# Copia_de_UC3844_-_CON_TEST.net
KiCad netlist of a schematic drawn in Altium Designer
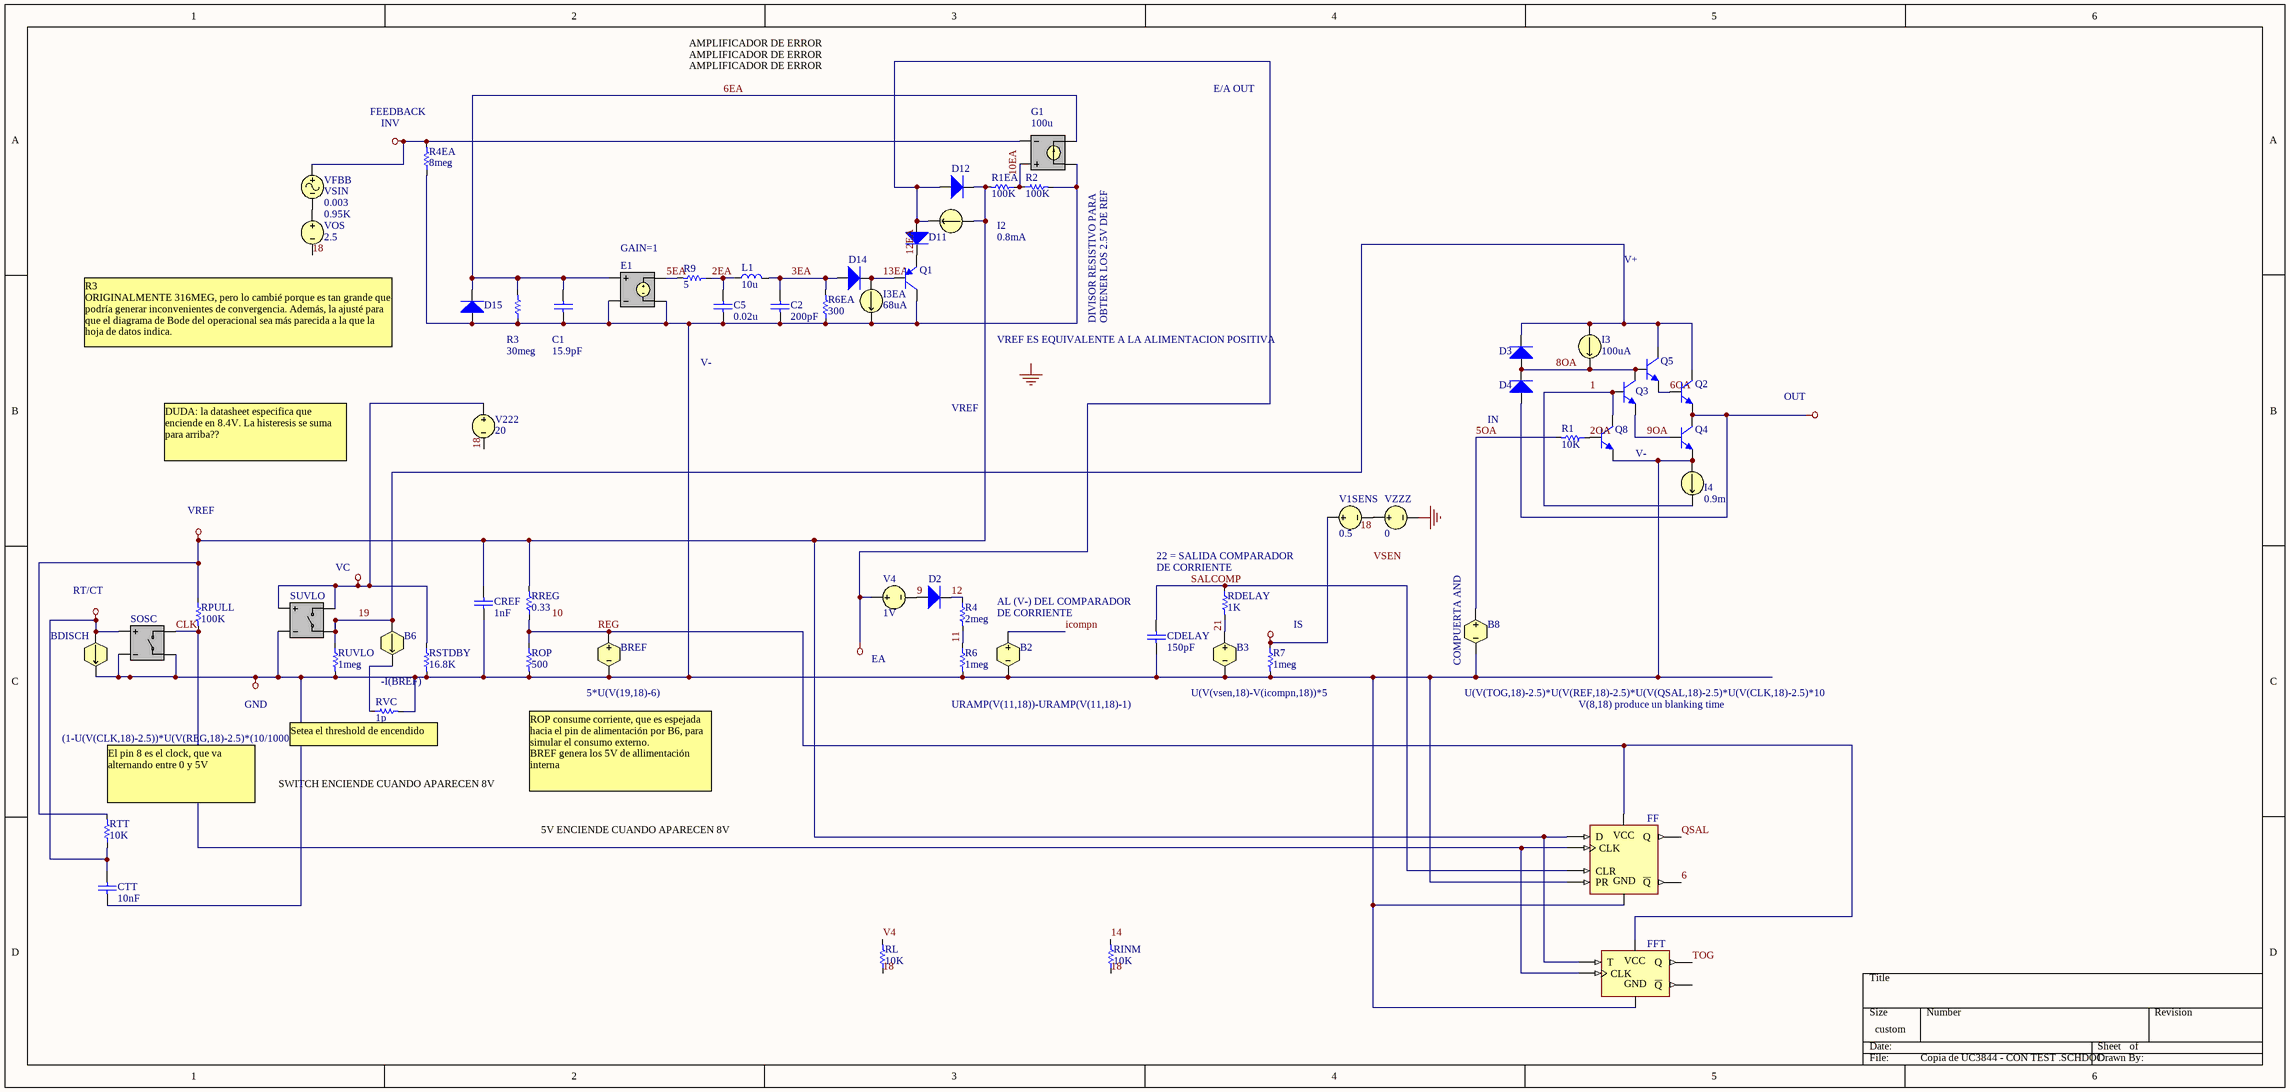
[diagram p0: Copia de UC3844 - CON TEST .SCHDOC]

(export (version "E")
  (design (tool "Eeschema 10.0.6"))
  (components
    (comp (ref "B2")
      (value "BVSRC")
      (description "Non-Linear Dependent Voltage Source")
      (fields
        (field (name "EQUATION") "URAMP(V(11,18))-URAMP(V(11,18)-1)")
        (field (name "PUBLISHER") "Altium Limited")
      )
      (libsource (lib "Simulation Sources") (part "BVSRC"))
    )
    (comp (ref "B3")
      (value "BVSRC")
      (description "Non-Linear Dependent Voltage Source")
      (fields
        (field (name "EQUATION") "U(V(vsen,18)-V(icompn,18))*5")
        (field (name "PUBLISHER") "Altium Limited")
      )
      (libsource (lib "Simulation Sources") (part "BVSRC"))
    )
    (comp (ref "B6")
      (value "BISRC")
      (description "Non-Linear Dependent Current Source")
      (fields (field (name "EQUATION") "-I(BREF)") (field (name "PUBLISHER") "Altium Limited"))
      (libsource (lib "Simulation Sources") (part "BISRC"))
    )
    (comp (ref "B8")
      (value "BVSRC")
      (description "Non-Linear Dependent Voltage Source")
      (fields
        (field (name "EQUATION") "U(V(TOG,18)-2.5)*U(V(REF,18)-2.5)*U(V(QSAL,18)-2.5)*U(V(CLK,18)-2.5)*10")
        (field (name "PUBLISHER") "Altium Limited")
      )
      (libsource (lib "Simulation Sources") (part "BVSRC"))
    )
    (comp (ref "BDISCH")
      (value "BISRC")
      (description "Non-Linear Dependent Current Source")
      (fields
        (field (name "EQUATION") "(1-U(V(CLK,18)-2.5))*U(V(REG,18)-2.5)*(10/1000)")
        (field (name "PUBLISHER") "Altium Limited")
      )
      (libsource (lib "Simulation Sources") (part "BISRC"))
    )
    (comp (ref "BREF")
      (value "BVSRC")
      (description "Non-Linear Dependent Voltage Source")
      (fields (field (name "EQUATION") "5*U(V(19,18)-6)") (field (name "PUBLISHER") "Altium Limited"))
      (libsource (lib "Simulation Sources") (part "BVSRC"))
    )
    (comp (ref "C1")
      (value "15.9pF")
      (footprint "0805")
      (description "Capacitor")
      (fields (field (name "VOLTAGE") "50V") (field (name "Comment") "Cap"))
      (libsource (lib "FEDE") (part "Cap"))
    )
    (comp (ref "C2")
      (value "200pF")
      (footprint "0805")
      (description "Capacitor")
      (fields (field (name "VOLTAGE") "50V") (field (name "Comment") "Cap"))
      (libsource (lib "FEDE") (part "Cap"))
    )
    (comp (ref "C5")
      (value "0.02u")
      (footprint "0805")
      (description "Capacitor")
      (fields (field (name "VOLTAGE") "50V") (field (name "Comment") "Cap"))
      (libsource (lib "FEDE") (part "Cap"))
    )
    (comp (ref "CDELAY")
      (value "150pF")
      (footprint "0805")
      (description "Capacitor")
      (fields (field (name "VOLTAGE") "50V") (field (name "Comment") "Cap"))
      (libsource (lib "FEDE") (part "Cap"))
    )
    (comp (ref "CREF")
      (value "1nF")
      (footprint "0805")
      (description "Capacitor")
      (fields (field (name "VOLTAGE") "50V") (field (name "Comment") "Cap"))
      (libsource (lib "FEDE") (part "Cap"))
    )
    (comp (ref "CTT")
      (value "10nF")
      (footprint "0805")
      (description "Capacitor")
      (fields (field (name "VOLTAGE") "50V") (field (name "Comment") "Cap"))
      (libsource (lib "FEDE") (part "Cap"))
    )
    (comp (ref "D2")
      (value "Diode")
      (footprint "diode400")
      (description "Diodo")
      (libsource (lib "FEDE") (part "Diode"))
    )
    (comp (ref "D3")
      (value "Diode")
      (footprint "diode400")
      (description "Diodo")
      (libsource (lib "FEDE") (part "Diode"))
    )
    (comp (ref "D4")
      (value "Diode")
      (footprint "diode400")
      (description "Diodo")
      (libsource (lib "FEDE") (part "Diode"))
    )
    (comp (ref "D11")
      (value "Diode")
      (footprint "diode400")
      (description "Diodo")
      (libsource (lib "FEDE") (part "Diode"))
    )
    (comp (ref "D12")
      (value "Diode")
      (footprint "diode400")
      (description "Diodo")
      (libsource (lib "FEDE") (part "Diode"))
    )
    (comp (ref "D14")
      (value "Diode")
      (footprint "diode400")
      (description "Diodo")
      (libsource (lib "FEDE") (part "Diode"))
    )
    (comp (ref "D15")
      (value "Diode")
      (footprint "diode400")
      (description "Diodo")
      (libsource (lib "FEDE") (part "Diode"))
    )
    (comp (ref "E1")
      (value "ESRC")
      (description "Voltage Controlled Voltage Source")
      (fields (field (name "PUBLISHER") "Altium Limited"))
      (libsource (lib "Simulation Sources") (part "ESRC"))
    )
    (comp (ref "FF")
      (value "FFSRV2")
      (description "D-Type Positive-Edge-Triggered Flip-Flop with Clear and Preset (simulación)")
      (libsource (lib "FEDE") (part "FFSRV2"))
    )
    (comp (ref "FFT")
      (value "FFT")
      (description "Positive-Edge-Triggered Flip-Flop T (simulación)")
      (libsource (lib "FEDE") (part "FFT"))
    )
    (comp (ref "G1")
      (value "GSRC")
      (description "Voltage Controlled Current Source")
      (fields (field (name "GAIN") "100u") (field (name "PUBLISHER") "Altium Limited"))
      (libsource (lib "Simulation Sources") (part "GSRC"))
    )
    (comp (ref "I2")
      (value "0.8mA")
      (description "Current Source")
      (fields (field (name "Comment") "ISRC") (field (name "PUBLISHER") "Altium Limited"))
      (libsource (lib "Simulation Sources") (part "ISRC"))
    )
    (comp (ref "I3")
      (value "100uA")
      (description "Current Source")
      (fields (field (name "Comment") "ISRC") (field (name "PUBLISHER") "Altium Limited"))
      (libsource (lib "Simulation Sources") (part "ISRC"))
    )
    (comp (ref "I3EA")
      (value "68uA")
      (description "Current Source")
      (fields (field (name "Comment") "ISRC") (field (name "PUBLISHER") "Altium Limited"))
      (libsource (lib "Simulation Sources") (part "ISRC"))
    )
    (comp (ref "I4")
      (value "0.9m")
      (description "Current Source")
      (fields (field (name "Comment") "ISRC") (field (name "PUBLISHER") "Altium Limited"))
      (libsource (lib "Simulation Sources") (part "ISRC"))
    )
    (comp (ref "L1")
      (value "10u")
      (footprint "TOROIDE TN14-9-5")
      (description "Inductor")
      (fields (field (name "Comment") "Inductor2"))
      (libsource (lib "FEDE") (part "Inductor2"))
    )
    (comp (ref "Q1")
      (value "PNP")
      (footprint "SOT23")
      (description "PNP Bipolar Transistor")
      (libsource (lib "FEDE") (part "PNP"))
    )
    (comp (ref "Q2")
      (value "NPN")
      (footprint "SOT23")
      (description "NPN Bipolar Transistor")
      (libsource (lib "FEDE") (part "NPN"))
    )
    (comp (ref "Q3")
      (value "NPN")
      (footprint "SOT23")
      (description "NPN Bipolar Transistor")
      (libsource (lib "FEDE") (part "NPN"))
    )
    (comp (ref "Q4")
      (value "NPN")
      (footprint "SOT23")
      (description "NPN Bipolar Transistor")
      (libsource (lib "FEDE") (part "NPN"))
    )
    (comp (ref "Q5")
      (value "NPN")
      (footprint "SOT23")
      (description "NPN Bipolar Transistor")
      (libsource (lib "FEDE") (part "NPN"))
    )
    (comp (ref "Q8")
      (value "NPN")
      (footprint "SOT23")
      (description "NPN Bipolar Transistor")
      (libsource (lib "FEDE") (part "NPN"))
    )
    (comp (ref "R1")
      (value "10K")
      (footprint "0805")
      (description "Resistor")
      (fields (field (name "POWER") "0.25W") (field (name "Comment") "Res"))
      (libsource (lib "FEDE") (part "Res"))
    )
    (comp (ref "R1EA")
      (value "100K")
      (footprint "0805")
      (description "Resistor")
      (fields (field (name "POWER") "0.25W") (field (name "Comment") "Res"))
      (libsource (lib "FEDE") (part "Res"))
    )
    (comp (ref "R2")
      (value "100K")
      (footprint "0805")
      (description "Resistor")
      (fields (field (name "POWER") "0.25W") (field (name "Comment") "Res"))
      (libsource (lib "FEDE") (part "Res"))
    )
    (comp (ref "R3")
      (value "30meg")
      (footprint "0805")
      (description "Resistor")
      (fields (field (name "POWER") "0.25W") (field (name "Comment") "Res"))
      (libsource (lib "FEDE") (part "Res"))
    )
    (comp (ref "R4")
      (value "2meg")
      (footprint "0805")
      (description "Resistor")
      (fields (field (name "POWER") "0.25W") (field (name "Comment") "Res"))
      (libsource (lib "FEDE") (part "Res"))
    )
    (comp (ref "R4EA")
      (value "8meg")
      (footprint "0805")
      (description "Resistor")
      (fields (field (name "POWER") "0.25W") (field (name "Comment") "Res"))
      (libsource (lib "FEDE") (part "Res"))
    )
    (comp (ref "R6")
      (value "1meg")
      (footprint "0805")
      (description "Resistor")
      (fields (field (name "POWER") "0.25W") (field (name "Comment") "Res"))
      (libsource (lib "FEDE") (part "Res"))
    )
    (comp (ref "R6EA")
      (value "300")
      (footprint "0805")
      (description "Resistor")
      (fields (field (name "POWER") "0.25W") (field (name "Comment") "Res"))
      (libsource (lib "FEDE") (part "Res"))
    )
    (comp (ref "R7")
      (value "1meg")
      (footprint "0805")
      (description "Resistor")
      (fields (field (name "POWER") "0.25W") (field (name "Comment") "Res"))
      (libsource (lib "FEDE") (part "Res"))
    )
    (comp (ref "R9")
      (value "5")
      (footprint "0805")
      (description "Resistor")
      (fields (field (name "POWER") "0.25W") (field (name "Comment") "Res"))
      (libsource (lib "FEDE") (part "Res"))
    )
    (comp (ref "RDELAY")
      (value "1K")
      (footprint "0805")
      (description "Resistor")
      (fields (field (name "POWER") "0.25W") (field (name "Comment") "Res"))
      (libsource (lib "FEDE") (part "Res"))
    )
    (comp (ref "RINM")
      (value "10K")
      (footprint "0805")
      (description "Resistor")
      (fields (field (name "POWER") "0.25W") (field (name "Comment") "Res"))
      (libsource (lib "FEDE") (part "Res"))
    )
    (comp (ref "RL")
      (value "10K")
      (footprint "0805")
      (description "Resistor")
      (fields (field (name "POWER") "0.25W") (field (name "Comment") "Res"))
      (libsource (lib "FEDE") (part "Res"))
    )
    (comp (ref "ROP")
      (value "500")
      (footprint "0805")
      (description "Resistor")
      (fields (field (name "POWER") "0.25W") (field (name "Comment") "Res"))
      (libsource (lib "FEDE") (part "Res"))
    )
    (comp (ref "RPULL")
      (value "100K")
      (footprint "0805")
      (description "Resistor")
      (fields (field (name "POWER") "0.25W") (field (name "Comment") "Res"))
      (libsource (lib "FEDE") (part "Res"))
    )
    (comp (ref "RREG")
      (value "0.33")
      (footprint "0805")
      (description "Resistor")
      (fields (field (name "POWER") "0.25W") (field (name "Comment") "Res"))
      (libsource (lib "FEDE") (part "Res"))
    )
    (comp (ref "RSTDBY")
      (value "16.8K")
      (footprint "0805")
      (description "Resistor")
      (fields (field (name "POWER") "0.25W") (field (name "Comment") "Res"))
      (libsource (lib "FEDE") (part "Res"))
    )
    (comp (ref "RTT")
      (value "10K")
      (footprint "0805")
      (description "Resistor")
      (fields (field (name "POWER") "0.25W") (field (name "Comment") "Res"))
      (libsource (lib "FEDE") (part "Res"))
    )
    (comp (ref "RUVLO")
      (value "1meg")
      (footprint "0805")
      (description "Resistor")
      (fields (field (name "POWER") "0.25W") (field (name "Comment") "Res"))
      (libsource (lib "FEDE") (part "Res"))
    )
    (comp (ref "RVC")
      (value "1p")
      (footprint "0805")
      (description "Resistor")
      (fields (field (name "POWER") "0.25W") (field (name "Comment") "Res"))
      (libsource (lib "FEDE") (part "Res"))
    )
    (comp (ref "SOSC")
      (value "VSW")
      (description "Voltage Controlled Switch (simulación)")
      (libsource (lib "FEDE") (part "VSW"))
    )
    (comp (ref "SUVLO")
      (value "VSW")
      (description "Voltage Controlled Switch (simulación)")
      (libsource (lib "FEDE") (part "VSW"))
    )
    (comp (ref "V1SENS")
      (value "0.5")
      (description "Voltage Source")
      (fields (field (name "Comment") "VSRC") (field (name "PUBLISHER") "Altium Limited"))
      (libsource (lib "Simulation Sources") (part "VSRC"))
    )
    (comp (ref "V4")
      (value "1V")
      (description "Voltage Source")
      (fields (field (name "Comment") "VSRC") (field (name "PUBLISHER") "Altium Limited"))
      (libsource (lib "Simulation Sources") (part "VSRC"))
    )
    (comp (ref "V222")
      (value "20")
      (description "Voltage Source")
      (fields (field (name "Comment") "VSRC") (field (name "PUBLISHER") "Altium Limited"))
      (libsource (lib "Simulation Sources") (part "VSRC"))
    )
    (comp (ref "VFBB")
      (value "VSIN")
      (description "Sinusoidal Voltage Source")
      (fields
        (field (name "AMPLITUDE") "0.003")
        (field (name "FREQUENCY") "0.95K")
        (field (name "PUBLISHER") "Altium Limited")
      )
      (libsource (lib "Simulation Sources") (part "VSIN"))
    )
    (comp (ref "VOS")
      (value "2.5")
      (description "Voltage Source")
      (fields (field (name "Comment") "VSRC") (field (name "PUBLISHER") "Altium Limited"))
      (libsource (lib "Simulation Sources") (part "VSRC"))
    )
    (comp (ref "VZZZ")
      (value "0")
      (description "Voltage Source")
      (fields (field (name "Comment") "VSRC") (field (name "PUBLISHER") "Altium Limited"))
      (libsource (lib "Simulation Sources") (part "VSRC"))
    )
  )
  (nets
    (net (code "1") (name "/1") (class "Default")
      (node (ref "I4") (pin "2") (pinfunction "2_2") (pintype "passive"))
      (node (ref "Q3") (pin "2") (pinfunction "B_2") (pintype "passive"))
      (node (ref "Q8") (pin "1") (pinfunction "C_1") (pintype "passive"))
    )
    (net (code "2") (name "/2EA") (class "Default")
      (node (ref "C5") (pin "2") (pinfunction "2_2") (pintype "passive"))
      (node (ref "L1") (pin "1") (pinfunction "1_1") (pintype "passive"))
      (node (ref "R9") (pin "1") (pinfunction "1_1") (pintype "passive"))
    )
    (net (code "3") (name "/2OA") (class "Default")
      (node (ref "Q8") (pin "2") (pinfunction "B_2") (pintype "passive"))
      (node (ref "R1") (pin "1") (pinfunction "1_1") (pintype "passive"))
    )
    (net (code "4") (name "/3EA") (class "Default")
      (node (ref "C2") (pin "2") (pinfunction "2_2") (pintype "passive"))
      (node (ref "D14") (pin "1") (pinfunction "1_1") (pintype "passive"))
      (node (ref "L1") (pin "2") (pinfunction "2_2") (pintype "passive"))
      (node (ref "R6EA") (pin "2") (pinfunction "2_2") (pintype "passive"))
    )
    (net (code "5") (name "/5EA") (class "Default")
      (node (ref "E1") (pin "3") (pinfunction "N+_3") (pintype "passive"))
      (node (ref "R9") (pin "2") (pinfunction "2_2") (pintype "passive"))
    )
    (net (code "6") (name "/5OA") (class "Default")
      (node (ref "B8") (pin "1") (pinfunction "1_1") (pintype "passive"))
      (node (ref "R1") (pin "2") (pinfunction "2_2") (pintype "passive"))
    )
    (net (code "7") (name "/6") (class "Default")
      (node (ref "FF") (pin "6") (pinfunction "~{Q}_6") (pintype "output"))
    )
    (net (code "8") (name "/6EA") (class "Default")
      (node (ref "C1") (pin "2") (pinfunction "2_2") (pintype "passive"))
      (node (ref "D15") (pin "2") (pinfunction "2_2") (pintype "passive"))
      (node (ref "E1") (pin "1") (pinfunction "NC+_1") (pintype "passive"))
      (node (ref "G1") (pin "4") (pinfunction "N-_4") (pintype "passive"))
      (node (ref "R3") (pin "2") (pinfunction "2_2") (pintype "passive"))
    )
    (net (code "9") (name "/6OA") (class "Default")
      (node (ref "Q2") (pin "2") (pinfunction "B_2") (pintype "passive"))
      (node (ref "Q5") (pin "3") (pinfunction "E_3") (pintype "passive"))
    )
    (net (code "10") (name "/8OA") (class "Default")
      (node (ref "D3") (pin "1") (pinfunction "1_1") (pintype "passive"))
      (node (ref "D4") (pin "2") (pinfunction "2_2") (pintype "passive"))
      (node (ref "I3") (pin "2") (pinfunction "2_2") (pintype "passive"))
      (node (ref "Q3") (pin "1") (pinfunction "C_1") (pintype "passive"))
      (node (ref "Q5") (pin "2") (pinfunction "B_2") (pintype "passive"))
    )
    (net (code "11") (name "/9") (class "Default")
      (node (ref "D2") (pin "1") (pinfunction "1_1") (pintype "passive"))
      (node (ref "V4") (pin "2") (pinfunction "2_2") (pintype "passive"))
    )
    (net (code "12") (name "/9OA") (class "Default")
      (node (ref "Q3") (pin "3") (pinfunction "E_3") (pintype "passive"))
      (node (ref "Q4") (pin "2") (pinfunction "B_2") (pintype "passive"))
    )
    (net (code "14") (name "/10EA") (class "Default")
      (node (ref "G1") (pin "1") (pinfunction "NC+_1") (pintype "passive"))
      (node (ref "R1EA") (pin "1") (pinfunction "1_1") (pintype "passive"))
      (node (ref "R2") (pin "1") (pinfunction "1_1") (pintype "passive"))
    )
    (net (code "15") (name "/11") (class "Default")
      (node (ref "R4") (pin "2") (pinfunction "2_2") (pintype "passive"))
      (node (ref "R6") (pin "1") (pinfunction "1_1") (pintype "passive"))
    )
    (net (code "16") (name "/12") (class "Default")
      (node (ref "D2") (pin "2") (pinfunction "2_2") (pintype "passive"))
      (node (ref "R4") (pin "1") (pinfunction "1_1") (pintype "passive"))
    )
    (net (code "17") (name "/12EA") (class "Default")
      (node (ref "D11") (pin "2") (pinfunction "2_2") (pintype "passive"))
      (node (ref "Q1") (pin "3") (pinfunction "E_3") (pintype "passive"))
    )
    (net (code "18") (name "/13EA") (class "Default")
      (node (ref "D14") (pin "2") (pinfunction "2_2") (pintype "passive"))
      (node (ref "I3EA") (pin "1") (pinfunction "1_1") (pintype "passive"))
      (node (ref "Q1") (pin "2") (pinfunction "B_2") (pintype "passive"))
    )
    (net (code "19") (name "/14") (class "Default")
      (node (ref "RINM") (pin "2") (pinfunction "2_2") (pintype "passive"))
    )
    (net (code "20") (name "/19") (class "Default")
      (node (ref "B6") (pin "1") (pinfunction "1_1") (pintype "passive"))
      (node (ref "D3") (pin "2") (pinfunction "2_2") (pintype "passive"))
      (node (ref "I3") (pin "1") (pinfunction "1_1") (pintype "passive"))
      (node (ref "Q2") (pin "1") (pinfunction "C_1") (pintype "passive"))
      (node (ref "Q5") (pin "1") (pinfunction "C_1") (pintype "passive"))
      (node (ref "RUVLO") (pin "1") (pinfunction "1_1") (pintype "passive"))
      (node (ref "SUVLO") (pin "4") (pinfunction "N2-_4") (pintype "passive"))
    )
    (net (code "21") (name "/21") (class "Default")
      (node (ref "B3") (pin "1") (pinfunction "1_1") (pintype "passive"))
      (node (ref "RDELAY") (pin "2") (pinfunction "2_2") (pintype "passive"))
    )
    (net (code "22") (name "/CLK") (class "Default")
      (node (ref "FF") (pin "3") (pinfunction "CLK_3") (pintype "input"))
      (node (ref "FFT") (pin "2") (pinfunction "CLK_2") (pintype "input"))
      (node (ref "RPULL") (pin "2") (pinfunction "2_2") (pintype "passive"))
      (node (ref "SOSC") (pin "3") (pinfunction "N2+_3") (pintype "passive"))
    )
    (net (code "23") (name "/QSAL") (class "Default")
      (node (ref "FF") (pin "5") (pinfunction "Q_5") (pintype "output"))
    )
    (net (code "24") (name "/REG") (class "Default")
      (node (ref "BREF") (pin "1") (pinfunction "1_1") (pintype "passive"))
      (node (ref "FF") (pin "14") (pinfunction "VCC_14") (pintype "power_in"))
      (node (ref "FFT") (pin "5") (pinfunction "VCC_5") (pintype "power_in"))
      (node (ref "ROP") (pin "1") (pinfunction "1_1") (pintype "passive"))
      (node (ref "RREG") (pin "1") (pinfunction "1_1") (pintype "passive"))
    )
    (net (code "25") (name "/SALCOMP") (class "Default")
      (node (ref "CDELAY") (pin "2") (pinfunction "2_2") (pintype "passive"))
      (node (ref "FF") (pin "1") (pinfunction "CLR_1") (pintype "input"))
      (node (ref "RDELAY") (pin "1") (pinfunction "1_1") (pintype "passive"))
    )
    (net (code "26") (name "/TOG") (class "Default")
      (node (ref "FFT") (pin "3") (pinfunction "Q_3") (pintype "output"))
    )
    (net (code "27") (name "/V4") (class "Default")
      (node (ref "RL") (pin "2") (pinfunction "2_2") (pintype "passive"))
    )
    (net (code "28") (name "/icompn") (class "Default")
      (node (ref "B2") (pin "1") (pinfunction "1_1") (pintype "passive"))
    )
    (net (code "29") (name "18") (class "Default")
      (node (ref "B2") (pin "2") (pinfunction "2_2") (pintype "passive"))
      (node (ref "B3") (pin "2") (pinfunction "2_2") (pintype "passive"))
      (node (ref "B8") (pin "2") (pinfunction "2_2") (pintype "passive"))
      (node (ref "BDISCH") (pin "2") (pinfunction "2_2") (pintype "passive"))
      (node (ref "BREF") (pin "2") (pinfunction "2_2") (pintype "passive"))
      (node (ref "C1") (pin "1") (pinfunction "1_1") (pintype "passive"))
      (node (ref "C2") (pin "1") (pinfunction "1_1") (pintype "passive"))
      (node (ref "C5") (pin "1") (pinfunction "1_1") (pintype "passive"))
      (node (ref "CDELAY") (pin "1") (pinfunction "1_1") (pintype "passive"))
      (node (ref "CREF") (pin "1") (pinfunction "1_1") (pintype "passive"))
      (node (ref "CTT") (pin "1") (pinfunction "1_1") (pintype "passive"))
      (node (ref "D15") (pin "1") (pinfunction "1_1") (pintype "passive"))
      (node (ref "E1") (pin "2") (pinfunction "NC-_2") (pintype "passive"))
      (node (ref "E1") (pin "4") (pinfunction "N-_4") (pintype "passive"))
      (node (ref "FF") (pin "4") (pinfunction "PR_4") (pintype "input"))
      (node (ref "FF") (pin "7") (pinfunction "GND_7") (pintype "power_in"))
      (node (ref "FFT") (pin "6") (pinfunction "GND_6") (pintype "power_in"))
      (node (ref "G1") (pin "3") (pinfunction "N+_3") (pintype "passive"))
      (node (ref "I3EA") (pin "2") (pinfunction "2_2") (pintype "passive"))
      (node (ref "I4") (pin "1") (pinfunction "1_1") (pintype "passive"))
      (node (ref "Q1") (pin "1") (pinfunction "C_1") (pintype "passive"))
      (node (ref "Q4") (pin "3") (pinfunction "E_3") (pintype "passive"))
      (node (ref "Q8") (pin "3") (pinfunction "E_3") (pintype "passive"))
      (node (ref "R2") (pin "2") (pinfunction "2_2") (pintype "passive"))
      (node (ref "R3") (pin "1") (pinfunction "1_1") (pintype "passive"))
      (node (ref "R4EA") (pin "1") (pinfunction "1_1") (pintype "passive"))
      (node (ref "R6") (pin "2") (pinfunction "2_2") (pintype "passive"))
      (node (ref "R6EA") (pin "1") (pinfunction "1_1") (pintype "passive"))
      (node (ref "R7") (pin "2") (pinfunction "2_2") (pintype "passive"))
      (node (ref "RINM") (pin "1") (pinfunction "1_1") (pintype "passive"))
      (node (ref "RL") (pin "1") (pinfunction "1_1") (pintype "passive"))
      (node (ref "ROP") (pin "2") (pinfunction "2_2") (pintype "passive"))
      (node (ref "RSTDBY") (pin "2") (pinfunction "2_2") (pintype "passive"))
      (node (ref "RUVLO") (pin "2") (pinfunction "2_2") (pintype "passive"))
      (node (ref "RVC") (pin "2") (pinfunction "2_2") (pintype "passive"))
      (node (ref "SOSC") (pin "2") (pinfunction "N1-_2") (pintype "passive"))
      (node (ref "SOSC") (pin "4") (pinfunction "N2-_4") (pintype "passive"))
      (node (ref "SUVLO") (pin "2") (pinfunction "N1-_2") (pintype "passive"))
      (node (ref "V1SENS") (pin "2") (pinfunction "2_2") (pintype "passive"))
      (node (ref "V222") (pin "2") (pinfunction "2_2") (pintype "passive"))
      (node (ref "VOS") (pin "2") (pinfunction "2_2") (pintype "passive"))
      (node (ref "VZZZ") (pin "1") (pinfunction "1_1") (pintype "passive"))
    )
    (net (code "30") (name "ALIM") (class "Default")
      (node (ref "RSTDBY") (pin "1") (pinfunction "1_1") (pintype "passive"))
      (node (ref "SUVLO") (pin "1") (pinfunction "N1+_1") (pintype "passive"))
      (node (ref "SUVLO") (pin "3") (pinfunction "N2+_3") (pintype "passive"))
      (node (ref "V222") (pin "1") (pinfunction "1_1") (pintype "passive"))
    )
    (net (code "31") (name "EAOUT") (class "Default")
      (node (ref "D11") (pin "1") (pinfunction "1_1") (pintype "passive"))
      (node (ref "D12") (pin "1") (pinfunction "1_1") (pintype "passive"))
      (node (ref "I2") (pin "2") (pinfunction "2_2") (pintype "passive"))
      (node (ref "V4") (pin "1") (pinfunction "1_1") (pintype "passive"))
    )
    (net (code "32") (name "FEED") (class "Default")
      (node (ref "G1") (pin "2") (pinfunction "NC-_2") (pintype "passive"))
      (node (ref "R4EA") (pin "2") (pinfunction "2_2") (pintype "passive"))
      (node (ref "VFBB") (pin "1") (pinfunction "1_1") (pintype "passive"))
    )
    (net (code "33") (name "GND") (class "Default")
      (node (ref "VZZZ") (pin "2") (pinfunction "2_2") (pintype "passive"))
    )
    (net (code "34") (name "Net-(B6-Pad2)") (class "Default")
      (node (ref "B6") (pin "2") (pinfunction "2_2") (pintype "passive"))
      (node (ref "RVC") (pin "1") (pinfunction "1_1") (pintype "passive"))
    )
    (net (code "35") (name "Net-(VFBB-Pad2)") (class "Default")
      (node (ref "VFBB") (pin "2") (pinfunction "2_2") (pintype "passive"))
      (node (ref "VOS") (pin "1") (pinfunction "1_1") (pintype "passive"))
    )
    (net (code "36") (name "OUT") (class "Default")
      (node (ref "D4") (pin "1") (pinfunction "1_1") (pintype "passive"))
      (node (ref "Q2") (pin "3") (pinfunction "E_3") (pintype "passive"))
      (node (ref "Q4") (pin "1") (pinfunction "C_1") (pintype "passive"))
    )
    (net (code "37") (name "REF") (class "Default")
      (node (ref "CREF") (pin "2") (pinfunction "2_2") (pintype "passive"))
      (node (ref "D12") (pin "2") (pinfunction "2_2") (pintype "passive"))
      (node (ref "FF") (pin "2") (pinfunction "D_2") (pintype "input"))
      (node (ref "FFT") (pin "1") (pinfunction "T_1") (pintype "input"))
      (node (ref "I2") (pin "1") (pinfunction "1_1") (pintype "passive"))
      (node (ref "R1EA") (pin "2") (pinfunction "2_2") (pintype "passive"))
      (node (ref "RPULL") (pin "1") (pinfunction "1_1") (pintype "passive"))
      (node (ref "RREG") (pin "2") (pinfunction "2_2") (pintype "passive"))
      (node (ref "RTT") (pin "2") (pinfunction "2_2") (pintype "passive"))
    )
    (net (code "38") (name "RTCT") (class "Default")
      (node (ref "BDISCH") (pin "1") (pinfunction "1_1") (pintype "passive"))
      (node (ref "CTT") (pin "2") (pinfunction "2_2") (pintype "passive"))
      (node (ref "RTT") (pin "1") (pinfunction "1_1") (pintype "passive"))
      (node (ref "SOSC") (pin "1") (pinfunction "N1+_1") (pintype "passive"))
    )
    (net (code "39") (name "VSEN") (class "Default")
      (node (ref "R7") (pin "1") (pinfunction "1_1") (pintype "passive"))
      (node (ref "V1SENS") (pin "1") (pinfunction "1_1") (pintype "passive"))
    )
    (net (code "40") (name "unconnected-(FFT-~{Q}-Pad4)") (class "Default")
      (node (ref "FFT") (pin "4") (pinfunction "~{Q}_4") (pintype "output"))
    )
  )
)
